# 1616.net
KiCad netlist of a schematic drawn in EAGLE
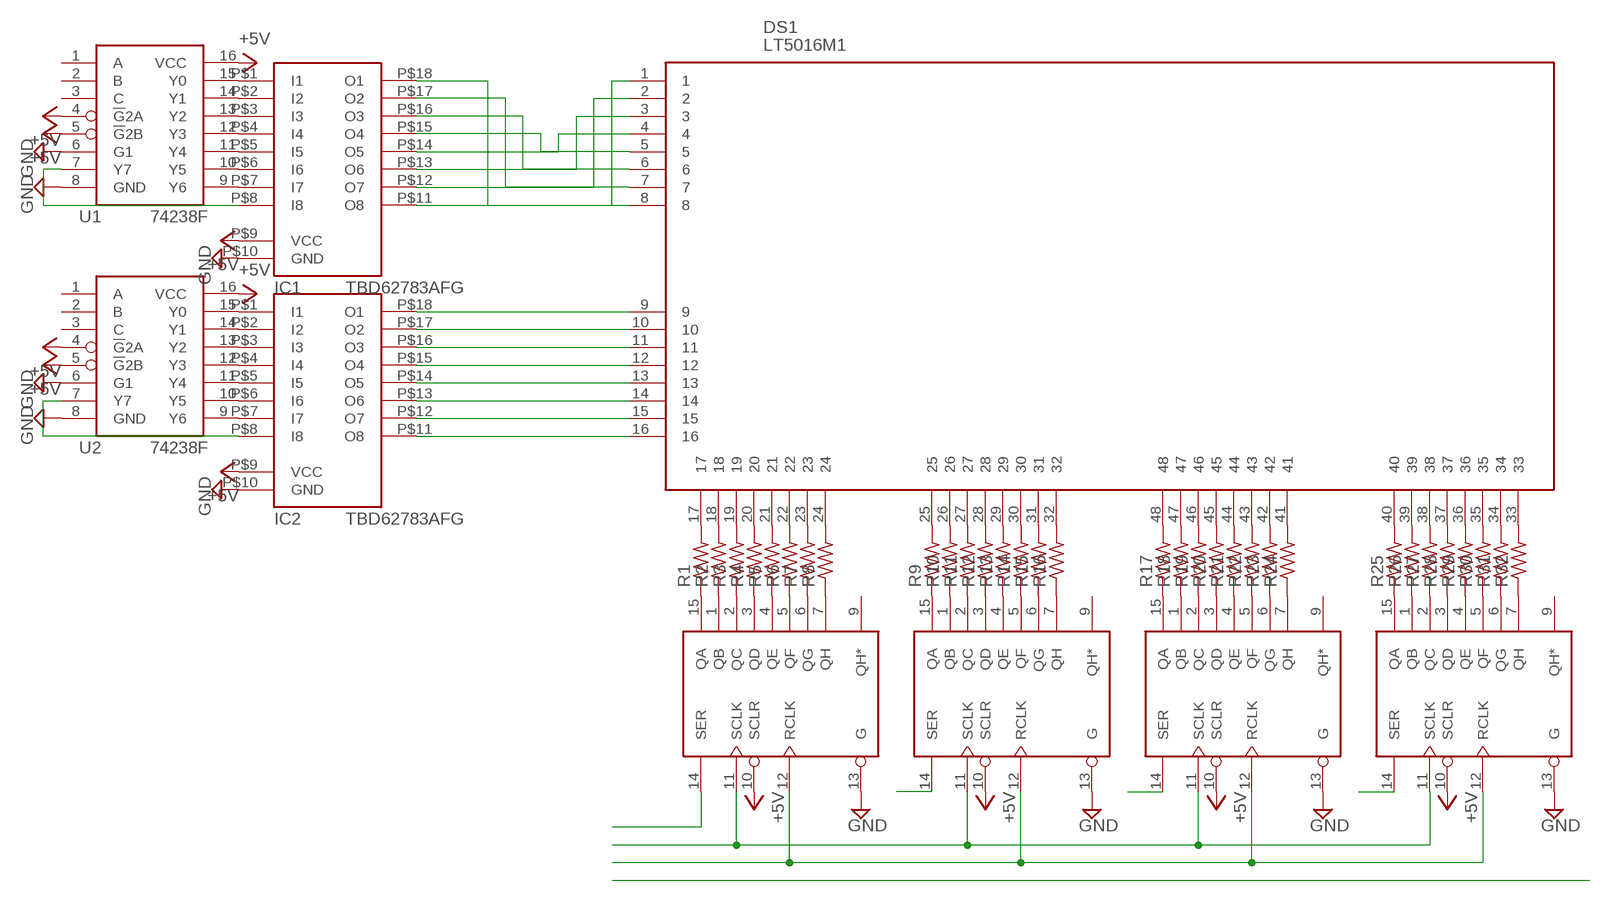
[diagram p0: schematic, sheet 1]

(export (version "E")
  (design (tool "Eeschema 10.0.6"))
  (components
    (comp (ref "DS1")
      (value "LT5016M1")
      (footprint "eagle-import:LT5016M1")
      (libsource (lib "eagle-import") (part "LT5016M1"))
    )
    (comp (ref "IC1")
      (value "TBD62783AFG")
      (footprint "eagle-import:SOP18")
      (libsource (lib "eagle-import") (part "TBD62783AFG"))
    )
    (comp (ref "IC2")
      (value "TBD62783AFG")
      (footprint "eagle-import:SOP18")
      (libsource (lib "eagle-import") (part "TBD62783AFG"))
    )
    (comp (ref "R1")
      (value "R-2012")
      (footprint "eagle-import:2012-R")
      (libsource (lib "eagle-import") (part "R-2012"))
    )
    (comp (ref "R2")
      (value "R-2012")
      (footprint "eagle-import:2012-R")
      (libsource (lib "eagle-import") (part "R-2012"))
    )
    (comp (ref "R3")
      (value "R-2012")
      (footprint "eagle-import:2012-R")
      (libsource (lib "eagle-import") (part "R-2012"))
    )
    (comp (ref "R4")
      (value "R-2012")
      (footprint "eagle-import:2012-R")
      (libsource (lib "eagle-import") (part "R-2012"))
    )
    (comp (ref "R5")
      (value "R-2012")
      (footprint "eagle-import:2012-R")
      (libsource (lib "eagle-import") (part "R-2012"))
    )
    (comp (ref "R6")
      (value "R-2012")
      (footprint "eagle-import:2012-R")
      (libsource (lib "eagle-import") (part "R-2012"))
    )
    (comp (ref "R7")
      (value "R-2012")
      (footprint "eagle-import:2012-R")
      (libsource (lib "eagle-import") (part "R-2012"))
    )
    (comp (ref "R8")
      (value "R-2012")
      (footprint "eagle-import:2012-R")
      (libsource (lib "eagle-import") (part "R-2012"))
    )
    (comp (ref "R9")
      (value "R-2012")
      (footprint "eagle-import:2012-R")
      (libsource (lib "eagle-import") (part "R-2012"))
    )
    (comp (ref "R10")
      (value "R-2012")
      (footprint "eagle-import:2012-R")
      (libsource (lib "eagle-import") (part "R-2012"))
    )
    (comp (ref "R11")
      (value "R-2012")
      (footprint "eagle-import:2012-R")
      (libsource (lib "eagle-import") (part "R-2012"))
    )
    (comp (ref "R12")
      (value "R-2012")
      (footprint "eagle-import:2012-R")
      (libsource (lib "eagle-import") (part "R-2012"))
    )
    (comp (ref "R13")
      (value "R-2012")
      (footprint "eagle-import:2012-R")
      (libsource (lib "eagle-import") (part "R-2012"))
    )
    (comp (ref "R14")
      (value "R-2012")
      (footprint "eagle-import:2012-R")
      (libsource (lib "eagle-import") (part "R-2012"))
    )
    (comp (ref "R15")
      (value "R-2012")
      (footprint "eagle-import:2012-R")
      (libsource (lib "eagle-import") (part "R-2012"))
    )
    (comp (ref "R16")
      (value "R-2012")
      (footprint "eagle-import:2012-R")
      (libsource (lib "eagle-import") (part "R-2012"))
    )
    (comp (ref "R17")
      (value "R-2012")
      (footprint "eagle-import:2012-R")
      (libsource (lib "eagle-import") (part "R-2012"))
    )
    (comp (ref "R18")
      (value "R-2012")
      (footprint "eagle-import:2012-R")
      (libsource (lib "eagle-import") (part "R-2012"))
    )
    (comp (ref "R19")
      (value "R-2012")
      (footprint "eagle-import:2012-R")
      (libsource (lib "eagle-import") (part "R-2012"))
    )
    (comp (ref "R20")
      (value "R-2012")
      (footprint "eagle-import:2012-R")
      (libsource (lib "eagle-import") (part "R-2012"))
    )
    (comp (ref "R21")
      (value "R-2012")
      (footprint "eagle-import:2012-R")
      (libsource (lib "eagle-import") (part "R-2012"))
    )
    (comp (ref "R22")
      (value "R-2012")
      (footprint "eagle-import:2012-R")
      (libsource (lib "eagle-import") (part "R-2012"))
    )
    (comp (ref "R23")
      (value "R-2012")
      (footprint "eagle-import:2012-R")
      (libsource (lib "eagle-import") (part "R-2012"))
    )
    (comp (ref "R24")
      (value "R-2012")
      (footprint "eagle-import:2012-R")
      (libsource (lib "eagle-import") (part "R-2012"))
    )
    (comp (ref "R25")
      (value "R-2012")
      (footprint "eagle-import:2012-R")
      (libsource (lib "eagle-import") (part "R-2012"))
    )
    (comp (ref "R26")
      (value "R-2012")
      (footprint "eagle-import:2012-R")
      (libsource (lib "eagle-import") (part "R-2012"))
    )
    (comp (ref "R27")
      (value "R-2012")
      (footprint "eagle-import:2012-R")
      (libsource (lib "eagle-import") (part "R-2012"))
    )
    (comp (ref "R28")
      (value "R-2012")
      (footprint "eagle-import:2012-R")
      (libsource (lib "eagle-import") (part "R-2012"))
    )
    (comp (ref "R29")
      (value "R-2012")
      (footprint "eagle-import:2012-R")
      (libsource (lib "eagle-import") (part "R-2012"))
    )
    (comp (ref "R30")
      (value "R-2012")
      (footprint "eagle-import:2012-R")
      (libsource (lib "eagle-import") (part "R-2012"))
    )
    (comp (ref "R31")
      (value "R-2012")
      (footprint "eagle-import:2012-R")
      (libsource (lib "eagle-import") (part "R-2012"))
    )
    (comp (ref "R32")
      (value "R-2012")
      (footprint "eagle-import:2012-R")
      (libsource (lib "eagle-import") (part "R-2012"))
    )
    (comp (ref "U$1")
      (value "74HC595N")
      (footprint "eagle-import:DIL16")
      (libsource (lib "eagle-import") (part "74595NHC"))
    )
    (comp (ref "U$2")
      (value "74HC595N")
      (footprint "eagle-import:DIL16")
      (libsource (lib "eagle-import") (part "74595NHC"))
    )
    (comp (ref "U$3")
      (value "74HC595N")
      (footprint "eagle-import:DIL16")
      (libsource (lib "eagle-import") (part "74595NHC"))
    )
    (comp (ref "U$4")
      (value "74HC595N")
      (footprint "eagle-import:DIL16")
      (libsource (lib "eagle-import") (part "74595NHC"))
    )
    (comp (ref "U1")
      (value "74238F")
      (footprint "eagle-import:SOP16")
      (libsource (lib "eagle-import") (part "74238F"))
    )
    (comp (ref "U2")
      (value "74238F")
      (footprint "eagle-import:SOP16")
      (libsource (lib "eagle-import") (part "74238F"))
    )
  )
  (nets
    (net (code "1") (name "+5V") (class "Default")
      (node (ref "IC1") (pin "P$9") (pinfunction "VCC_P$9") (pintype "power_in"))
      (node (ref "IC2") (pin "P$9") (pinfunction "VCC_P$9") (pintype "power_in"))
      (node (ref "U$1") (pin "10") (pinfunction "SCLR_10") (pintype "input"))
      (node (ref "U$2") (pin "10") (pinfunction "SCLR_10") (pintype "input"))
      (node (ref "U$3") (pin "10") (pinfunction "SCLR_10") (pintype "input"))
      (node (ref "U$4") (pin "10") (pinfunction "SCLR_10") (pintype "input"))
      (node (ref "U1") (pin "16") (pinfunction "VCC_16") (pintype "power_in"))
      (node (ref "U1") (pin "4") (pinfunction "~{G}2A_4") (pintype "input"))
      (node (ref "U1") (pin "5") (pinfunction "~{G}2B_5") (pintype "input"))
      (node (ref "U2") (pin "16") (pinfunction "VCC_16") (pintype "power_in"))
      (node (ref "U2") (pin "4") (pinfunction "~{G}2A_4") (pintype "input"))
      (node (ref "U2") (pin "5") (pinfunction "~{G}2B_5") (pintype "input"))
    )
    (net (code "2") (name "GND") (class "Default")
      (node (ref "IC1") (pin "P$10") (pinfunction "GND_P$10") (pintype "power_in"))
      (node (ref "IC2") (pin "P$10") (pinfunction "GND_P$10") (pintype "power_in"))
      (node (ref "U$1") (pin "13") (pinfunction "G_13") (pintype "input"))
      (node (ref "U$2") (pin "13") (pinfunction "G_13") (pintype "input"))
      (node (ref "U$3") (pin "13") (pinfunction "G_13") (pintype "input"))
      (node (ref "U$4") (pin "13") (pinfunction "G_13") (pintype "input"))
      (node (ref "U1") (pin "6") (pinfunction "G1_6") (pintype "input"))
      (node (ref "U1") (pin "8") (pinfunction "GND_8") (pintype "power_in"))
      (node (ref "U2") (pin "6") (pinfunction "G1_6") (pintype "input"))
      (node (ref "U2") (pin "8") (pinfunction "GND_8") (pintype "power_in"))
    )
    (net (code "3") (name "Net-(DS1-Pad17)") (class "Default")
      (node (ref "DS1") (pin "17") (pinfunction "17_17") (pintype "bidirectional"))
      (node (ref "R1") (pin "2") (pinfunction "2_2") (pintype "passive"))
    )
    (net (code "4") (name "Net-(DS1-Pad18)") (class "Default")
      (node (ref "DS1") (pin "18") (pinfunction "18_18") (pintype "bidirectional"))
      (node (ref "R2") (pin "2") (pinfunction "2_2") (pintype "passive"))
    )
    (net (code "5") (name "Net-(DS1-Pad19)") (class "Default")
      (node (ref "DS1") (pin "19") (pinfunction "19_19") (pintype "bidirectional"))
      (node (ref "R3") (pin "2") (pinfunction "2_2") (pintype "passive"))
    )
    (net (code "6") (name "Net-(DS1-Pad20)") (class "Default")
      (node (ref "DS1") (pin "20") (pinfunction "20_20") (pintype "bidirectional"))
      (node (ref "R4") (pin "2") (pinfunction "2_2") (pintype "passive"))
    )
    (net (code "7") (name "Net-(DS1-Pad21)") (class "Default")
      (node (ref "DS1") (pin "21") (pinfunction "21_21") (pintype "bidirectional"))
      (node (ref "R5") (pin "2") (pinfunction "2_2") (pintype "passive"))
    )
    (net (code "8") (name "Net-(DS1-Pad22)") (class "Default")
      (node (ref "DS1") (pin "22") (pinfunction "22_22") (pintype "bidirectional"))
      (node (ref "R6") (pin "2") (pinfunction "2_2") (pintype "passive"))
    )
    (net (code "9") (name "Net-(DS1-Pad23)") (class "Default")
      (node (ref "DS1") (pin "23") (pinfunction "23_23") (pintype "bidirectional"))
      (node (ref "R7") (pin "2") (pinfunction "2_2") (pintype "passive"))
    )
    (net (code "10") (name "Net-(DS1-Pad24)") (class "Default")
      (node (ref "DS1") (pin "24") (pinfunction "24_24") (pintype "bidirectional"))
      (node (ref "R8") (pin "2") (pinfunction "2_2") (pintype "passive"))
    )
    (net (code "11") (name "Net-(DS1-Pad25)") (class "Default")
      (node (ref "DS1") (pin "25") (pinfunction "25_25") (pintype "bidirectional"))
      (node (ref "R9") (pin "2") (pinfunction "2_2") (pintype "passive"))
    )
    (net (code "12") (name "Net-(DS1-Pad26)") (class "Default")
      (node (ref "DS1") (pin "26") (pinfunction "26_26") (pintype "bidirectional"))
      (node (ref "R10") (pin "2") (pinfunction "2_2") (pintype "passive"))
    )
    (net (code "13") (name "Net-(DS1-Pad27)") (class "Default")
      (node (ref "DS1") (pin "27") (pinfunction "27_27") (pintype "bidirectional"))
      (node (ref "R11") (pin "2") (pinfunction "2_2") (pintype "passive"))
    )
    (net (code "14") (name "Net-(DS1-Pad28)") (class "Default")
      (node (ref "DS1") (pin "28") (pinfunction "28_28") (pintype "bidirectional"))
      (node (ref "R12") (pin "2") (pinfunction "2_2") (pintype "passive"))
    )
    (net (code "15") (name "Net-(DS1-Pad29)") (class "Default")
      (node (ref "DS1") (pin "29") (pinfunction "29_29") (pintype "bidirectional"))
      (node (ref "R13") (pin "2") (pinfunction "2_2") (pintype "passive"))
    )
    (net (code "16") (name "Net-(DS1-Pad30)") (class "Default")
      (node (ref "DS1") (pin "30") (pinfunction "30_30") (pintype "bidirectional"))
      (node (ref "R14") (pin "2") (pinfunction "2_2") (pintype "passive"))
    )
    (net (code "17") (name "Net-(DS1-Pad31)") (class "Default")
      (node (ref "DS1") (pin "31") (pinfunction "31_31") (pintype "bidirectional"))
      (node (ref "R15") (pin "2") (pinfunction "2_2") (pintype "passive"))
    )
    (net (code "18") (name "Net-(DS1-Pad32)") (class "Default")
      (node (ref "DS1") (pin "32") (pinfunction "32_32") (pintype "bidirectional"))
      (node (ref "R16") (pin "2") (pinfunction "2_2") (pintype "passive"))
    )
    (net (code "19") (name "Net-(DS1-Pad33)") (class "Default")
      (node (ref "DS1") (pin "33") (pinfunction "33_33") (pintype "bidirectional"))
      (node (ref "R32") (pin "2") (pinfunction "2_2") (pintype "passive"))
    )
    (net (code "20") (name "Net-(DS1-Pad34)") (class "Default")
      (node (ref "DS1") (pin "34") (pinfunction "34_34") (pintype "bidirectional"))
      (node (ref "R31") (pin "2") (pinfunction "2_2") (pintype "passive"))
    )
    (net (code "21") (name "Net-(DS1-Pad35)") (class "Default")
      (node (ref "DS1") (pin "35") (pinfunction "35_35") (pintype "bidirectional"))
      (node (ref "R30") (pin "2") (pinfunction "2_2") (pintype "passive"))
    )
    (net (code "22") (name "Net-(DS1-Pad36)") (class "Default")
      (node (ref "DS1") (pin "36") (pinfunction "36_36") (pintype "bidirectional"))
      (node (ref "R29") (pin "2") (pinfunction "2_2") (pintype "passive"))
    )
    (net (code "23") (name "Net-(DS1-Pad37)") (class "Default")
      (node (ref "DS1") (pin "37") (pinfunction "37_37") (pintype "bidirectional"))
      (node (ref "R28") (pin "2") (pinfunction "2_2") (pintype "passive"))
    )
    (net (code "24") (name "Net-(DS1-Pad38)") (class "Default")
      (node (ref "DS1") (pin "38") (pinfunction "38_38") (pintype "bidirectional"))
      (node (ref "R27") (pin "2") (pinfunction "2_2") (pintype "passive"))
    )
    (net (code "25") (name "Net-(DS1-Pad39)") (class "Default")
      (node (ref "DS1") (pin "39") (pinfunction "39_39") (pintype "bidirectional"))
      (node (ref "R26") (pin "2") (pinfunction "2_2") (pintype "passive"))
    )
    (net (code "26") (name "Net-(DS1-Pad40)") (class "Default")
      (node (ref "DS1") (pin "40") (pinfunction "40_40") (pintype "bidirectional"))
      (node (ref "R25") (pin "2") (pinfunction "2_2") (pintype "passive"))
    )
    (net (code "27") (name "Net-(DS1-Pad41)") (class "Default")
      (node (ref "DS1") (pin "41") (pinfunction "41_41") (pintype "bidirectional"))
      (node (ref "R24") (pin "2") (pinfunction "2_2") (pintype "passive"))
    )
    (net (code "28") (name "Net-(DS1-Pad42)") (class "Default")
      (node (ref "DS1") (pin "42") (pinfunction "42_42") (pintype "bidirectional"))
      (node (ref "R23") (pin "2") (pinfunction "2_2") (pintype "passive"))
    )
    (net (code "29") (name "Net-(DS1-Pad43)") (class "Default")
      (node (ref "DS1") (pin "43") (pinfunction "43_43") (pintype "bidirectional"))
      (node (ref "R22") (pin "2") (pinfunction "2_2") (pintype "passive"))
    )
    (net (code "30") (name "Net-(DS1-Pad44)") (class "Default")
      (node (ref "DS1") (pin "44") (pinfunction "44_44") (pintype "bidirectional"))
      (node (ref "R21") (pin "2") (pinfunction "2_2") (pintype "passive"))
    )
    (net (code "31") (name "Net-(DS1-Pad45)") (class "Default")
      (node (ref "DS1") (pin "45") (pinfunction "45_45") (pintype "bidirectional"))
      (node (ref "R20") (pin "2") (pinfunction "2_2") (pintype "passive"))
    )
    (net (code "32") (name "Net-(DS1-Pad46)") (class "Default")
      (node (ref "DS1") (pin "46") (pinfunction "46_46") (pintype "bidirectional"))
      (node (ref "R19") (pin "2") (pinfunction "2_2") (pintype "passive"))
    )
    (net (code "33") (name "Net-(DS1-Pad47)") (class "Default")
      (node (ref "DS1") (pin "47") (pinfunction "47_47") (pintype "bidirectional"))
      (node (ref "R18") (pin "2") (pinfunction "2_2") (pintype "passive"))
    )
    (net (code "34") (name "Net-(DS1-Pad48)") (class "Default")
      (node (ref "DS1") (pin "48") (pinfunction "48_48") (pintype "bidirectional"))
      (node (ref "R17") (pin "2") (pinfunction "2_2") (pintype "passive"))
    )
    (net (code "35") (name "Net-(IC1-I1)") (class "Default")
      (node (ref "IC1") (pin "P$1") (pinfunction "I1_P$1") (pintype "input"))
      (node (ref "U1") (pin "15") (pinfunction "Y0_15") (pintype "output"))
    )
    (net (code "36") (name "Net-(IC1-I2)") (class "Default")
      (node (ref "IC1") (pin "P$2") (pinfunction "I2_P$2") (pintype "input"))
      (node (ref "U1") (pin "14") (pinfunction "Y1_14") (pintype "output"))
    )
    (net (code "37") (name "Net-(IC1-I3)") (class "Default")
      (node (ref "IC1") (pin "P$3") (pinfunction "I3_P$3") (pintype "input"))
      (node (ref "U1") (pin "13") (pinfunction "Y2_13") (pintype "output"))
    )
    (net (code "38") (name "Net-(IC1-I4)") (class "Default")
      (node (ref "IC1") (pin "P$4") (pinfunction "I4_P$4") (pintype "input"))
      (node (ref "U1") (pin "12") (pinfunction "Y3_12") (pintype "output"))
    )
    (net (code "39") (name "Net-(IC1-I5)") (class "Default")
      (node (ref "IC1") (pin "P$5") (pinfunction "I5_P$5") (pintype "input"))
      (node (ref "U1") (pin "11") (pinfunction "Y4_11") (pintype "output"))
    )
    (net (code "40") (name "Net-(IC1-I6)") (class "Default")
      (node (ref "IC1") (pin "P$6") (pinfunction "I6_P$6") (pintype "input"))
      (node (ref "U1") (pin "10") (pinfunction "Y5_10") (pintype "output"))
    )
    (net (code "41") (name "Net-(IC1-I7)") (class "Default")
      (node (ref "IC1") (pin "P$7") (pinfunction "I7_P$7") (pintype "input"))
      (node (ref "U1") (pin "9") (pinfunction "Y6_9") (pintype "output"))
    )
    (net (code "42") (name "Net-(IC1-I8)") (class "Default")
      (node (ref "IC1") (pin "P$8") (pinfunction "I8_P$8") (pintype "input"))
      (node (ref "U1") (pin "7") (pinfunction "Y7_7") (pintype "output"))
    )
    (net (code "43") (name "Net-(IC1-O1)") (class "Default")
      (node (ref "DS1") (pin "8") (pinfunction "8_8") (pintype "bidirectional"))
      (node (ref "IC1") (pin "P$18") (pinfunction "O1_P$18") (pintype "output"))
    )
    (net (code "44") (name "Net-(IC1-O2)") (class "Default")
      (node (ref "DS1") (pin "7") (pinfunction "7_7") (pintype "bidirectional"))
      (node (ref "IC1") (pin "P$17") (pinfunction "O2_P$17") (pintype "output"))
    )
    (net (code "45") (name "Net-(IC1-O3)") (class "Default")
      (node (ref "DS1") (pin "6") (pinfunction "6_6") (pintype "bidirectional"))
      (node (ref "IC1") (pin "P$16") (pinfunction "O3_P$16") (pintype "output"))
    )
    (net (code "46") (name "Net-(IC1-O4)") (class "Default")
      (node (ref "DS1") (pin "5") (pinfunction "5_5") (pintype "bidirectional"))
      (node (ref "IC1") (pin "P$15") (pinfunction "O4_P$15") (pintype "output"))
    )
    (net (code "47") (name "Net-(IC1-O5)") (class "Default")
      (node (ref "DS1") (pin "4") (pinfunction "4_4") (pintype "bidirectional"))
      (node (ref "IC1") (pin "P$14") (pinfunction "O5_P$14") (pintype "output"))
    )
    (net (code "48") (name "Net-(IC1-O6)") (class "Default")
      (node (ref "DS1") (pin "3") (pinfunction "3_3") (pintype "bidirectional"))
      (node (ref "IC1") (pin "P$13") (pinfunction "O6_P$13") (pintype "output"))
    )
    (net (code "49") (name "Net-(IC1-O7)") (class "Default")
      (node (ref "DS1") (pin "2") (pinfunction "2_2") (pintype "bidirectional"))
      (node (ref "IC1") (pin "P$12") (pinfunction "O7_P$12") (pintype "output"))
    )
    (net (code "50") (name "Net-(IC1-O8)") (class "Default")
      (node (ref "DS1") (pin "1") (pinfunction "1_1") (pintype "bidirectional"))
      (node (ref "IC1") (pin "P$11") (pinfunction "O8_P$11") (pintype "output"))
    )
    (net (code "51") (name "Net-(IC2-I1)") (class "Default")
      (node (ref "IC2") (pin "P$1") (pinfunction "I1_P$1") (pintype "input"))
      (node (ref "U2") (pin "15") (pinfunction "Y0_15") (pintype "output"))
    )
    (net (code "52") (name "Net-(IC2-I2)") (class "Default")
      (node (ref "IC2") (pin "P$2") (pinfunction "I2_P$2") (pintype "input"))
      (node (ref "U2") (pin "14") (pinfunction "Y1_14") (pintype "output"))
    )
    (net (code "53") (name "Net-(IC2-I3)") (class "Default")
      (node (ref "IC2") (pin "P$3") (pinfunction "I3_P$3") (pintype "input"))
      (node (ref "U2") (pin "13") (pinfunction "Y2_13") (pintype "output"))
    )
    (net (code "54") (name "Net-(IC2-I4)") (class "Default")
      (node (ref "IC2") (pin "P$4") (pinfunction "I4_P$4") (pintype "input"))
      (node (ref "U2") (pin "12") (pinfunction "Y3_12") (pintype "output"))
    )
    (net (code "55") (name "Net-(IC2-I5)") (class "Default")
      (node (ref "IC2") (pin "P$5") (pinfunction "I5_P$5") (pintype "input"))
      (node (ref "U2") (pin "11") (pinfunction "Y4_11") (pintype "output"))
    )
    (net (code "56") (name "Net-(IC2-I6)") (class "Default")
      (node (ref "IC2") (pin "P$6") (pinfunction "I6_P$6") (pintype "input"))
      (node (ref "U2") (pin "10") (pinfunction "Y5_10") (pintype "output"))
    )
    (net (code "57") (name "Net-(IC2-I7)") (class "Default")
      (node (ref "IC2") (pin "P$7") (pinfunction "I7_P$7") (pintype "input"))
      (node (ref "U2") (pin "9") (pinfunction "Y6_9") (pintype "output"))
    )
    (net (code "58") (name "Net-(IC2-I8)") (class "Default")
      (node (ref "IC2") (pin "P$8") (pinfunction "I8_P$8") (pintype "input"))
      (node (ref "U2") (pin "7") (pinfunction "Y7_7") (pintype "output"))
    )
    (net (code "59") (name "Net-(IC2-O1)") (class "Default")
      (node (ref "DS1") (pin "9") (pinfunction "9_9") (pintype "bidirectional"))
      (node (ref "IC2") (pin "P$18") (pinfunction "O1_P$18") (pintype "output"))
    )
    (net (code "60") (name "Net-(IC2-O2)") (class "Default")
      (node (ref "DS1") (pin "10") (pinfunction "10_10") (pintype "bidirectional"))
      (node (ref "IC2") (pin "P$17") (pinfunction "O2_P$17") (pintype "output"))
    )
    (net (code "61") (name "Net-(IC2-O3)") (class "Default")
      (node (ref "DS1") (pin "11") (pinfunction "11_11") (pintype "bidirectional"))
      (node (ref "IC2") (pin "P$16") (pinfunction "O3_P$16") (pintype "output"))
    )
    (net (code "62") (name "Net-(IC2-O4)") (class "Default")
      (node (ref "DS1") (pin "12") (pinfunction "12_12") (pintype "bidirectional"))
      (node (ref "IC2") (pin "P$15") (pinfunction "O4_P$15") (pintype "output"))
    )
    (net (code "63") (name "Net-(IC2-O5)") (class "Default")
      (node (ref "DS1") (pin "13") (pinfunction "13_13") (pintype "bidirectional"))
      (node (ref "IC2") (pin "P$14") (pinfunction "O5_P$14") (pintype "output"))
    )
    (net (code "64") (name "Net-(IC2-O6)") (class "Default")
      (node (ref "DS1") (pin "14") (pinfunction "14_14") (pintype "bidirectional"))
      (node (ref "IC2") (pin "P$13") (pinfunction "O6_P$13") (pintype "output"))
    )
    (net (code "65") (name "Net-(IC2-O7)") (class "Default")
      (node (ref "DS1") (pin "15") (pinfunction "15_15") (pintype "bidirectional"))
      (node (ref "IC2") (pin "P$12") (pinfunction "O7_P$12") (pintype "output"))
    )
    (net (code "66") (name "Net-(IC2-O8)") (class "Default")
      (node (ref "DS1") (pin "16") (pinfunction "16_16") (pintype "bidirectional"))
      (node (ref "IC2") (pin "P$11") (pinfunction "O8_P$11") (pintype "output"))
    )
    (net (code "67") (name "Net-(U$1A-QA)") (class "Default")
      (node (ref "R1") (pin "1") (pinfunction "1_1") (pintype "passive"))
      (node (ref "U$1") (pin "15") (pinfunction "QA_15") (pintype "output"))
    )
    (net (code "68") (name "Net-(U$1A-QB)") (class "Default")
      (node (ref "R2") (pin "1") (pinfunction "1_1") (pintype "passive"))
      (node (ref "U$1") (pin "1") (pinfunction "QB_1") (pintype "output"))
    )
    (net (code "69") (name "Net-(U$1A-QC)") (class "Default")
      (node (ref "R3") (pin "1") (pinfunction "1_1") (pintype "passive"))
      (node (ref "U$1") (pin "2") (pinfunction "QC_2") (pintype "output"))
    )
    (net (code "70") (name "Net-(U$1A-QD)") (class "Default")
      (node (ref "R4") (pin "1") (pinfunction "1_1") (pintype "passive"))
      (node (ref "U$1") (pin "3") (pinfunction "QD_3") (pintype "output"))
    )
    (net (code "71") (name "Net-(U$1A-QE)") (class "Default")
      (node (ref "R5") (pin "1") (pinfunction "1_1") (pintype "passive"))
      (node (ref "U$1") (pin "4") (pinfunction "QE_4") (pintype "output"))
    )
    (net (code "72") (name "Net-(U$1A-QF)") (class "Default")
      (node (ref "R6") (pin "1") (pinfunction "1_1") (pintype "passive"))
      (node (ref "U$1") (pin "5") (pinfunction "QF_5") (pintype "output"))
    )
    (net (code "73") (name "Net-(U$1A-QG)") (class "Default")
      (node (ref "R7") (pin "1") (pinfunction "1_1") (pintype "passive"))
      (node (ref "U$1") (pin "6") (pinfunction "QG_6") (pintype "output"))
    )
    (net (code "74") (name "Net-(U$1A-QH)") (class "Default")
      (node (ref "R8") (pin "1") (pinfunction "1_1") (pintype "passive"))
      (node (ref "U$1") (pin "7") (pinfunction "QH_7") (pintype "output"))
    )
    (net (code "75") (name "Net-(U$1A-RCLK)") (class "Default")
      (node (ref "U$1") (pin "12") (pinfunction "RCLK_12") (pintype "input"))
      (node (ref "U$2") (pin "12") (pinfunction "RCLK_12") (pintype "input"))
      (node (ref "U$3") (pin "12") (pinfunction "RCLK_12") (pintype "input"))
      (node (ref "U$4") (pin "12") (pinfunction "RCLK_12") (pintype "input"))
    )
    (net (code "76") (name "Net-(U$1A-SCLK)") (class "Default")
      (node (ref "U$1") (pin "11") (pinfunction "SCLK_11") (pintype "input"))
      (node (ref "U$2") (pin "11") (pinfunction "SCLK_11") (pintype "input"))
      (node (ref "U$3") (pin "11") (pinfunction "SCLK_11") (pintype "input"))
      (node (ref "U$4") (pin "11") (pinfunction "SCLK_11") (pintype "input"))
    )
    (net (code "77") (name "Net-(U$2A-QA)") (class "Default")
      (node (ref "R9") (pin "1") (pinfunction "1_1") (pintype "passive"))
      (node (ref "U$2") (pin "15") (pinfunction "QA_15") (pintype "output"))
    )
    (net (code "78") (name "Net-(U$2A-QB)") (class "Default")
      (node (ref "R10") (pin "1") (pinfunction "1_1") (pintype "passive"))
      (node (ref "U$2") (pin "1") (pinfunction "QB_1") (pintype "output"))
    )
    (net (code "79") (name "Net-(U$2A-QC)") (class "Default")
      (node (ref "R11") (pin "1") (pinfunction "1_1") (pintype "passive"))
      (node (ref "U$2") (pin "2") (pinfunction "QC_2") (pintype "output"))
    )
    (net (code "80") (name "Net-(U$2A-QD)") (class "Default")
      (node (ref "R12") (pin "1") (pinfunction "1_1") (pintype "passive"))
      (node (ref "U$2") (pin "3") (pinfunction "QD_3") (pintype "output"))
    )
    (net (code "81") (name "Net-(U$2A-QE)") (class "Default")
      (node (ref "R13") (pin "1") (pinfunction "1_1") (pintype "passive"))
      (node (ref "U$2") (pin "4") (pinfunction "QE_4") (pintype "output"))
    )
    (net (code "82") (name "Net-(U$2A-QF)") (class "Default")
      (node (ref "R14") (pin "1") (pinfunction "1_1") (pintype "passive"))
      (node (ref "U$2") (pin "5") (pinfunction "QF_5") (pintype "output"))
    )
    (net (code "83") (name "Net-(U$2A-QG)") (class "Default")
      (node (ref "R15") (pin "1") (pinfunction "1_1") (pintype "passive"))
      (node (ref "U$2") (pin "6") (pinfunction "QG_6") (pintype "output"))
    )
    (net (code "84") (name "Net-(U$2A-QH)") (class "Default")
      (node (ref "R16") (pin "1") (pinfunction "1_1") (pintype "passive"))
      (node (ref "U$2") (pin "7") (pinfunction "QH_7") (pintype "output"))
    )
    (net (code "85") (name "Net-(U$3A-QA)") (class "Default")
      (node (ref "R17") (pin "1") (pinfunction "1_1") (pintype "passive"))
      (node (ref "U$3") (pin "15") (pinfunction "QA_15") (pintype "output"))
    )
    (net (code "86") (name "Net-(U$3A-QB)") (class "Default")
      (node (ref "R18") (pin "1") (pinfunction "1_1") (pintype "passive"))
      (node (ref "U$3") (pin "1") (pinfunction "QB_1") (pintype "output"))
    )
    (net (code "87") (name "Net-(U$3A-QC)") (class "Default")
      (node (ref "R19") (pin "1") (pinfunction "1_1") (pintype "passive"))
      (node (ref "U$3") (pin "2") (pinfunction "QC_2") (pintype "output"))
    )
    (net (code "88") (name "Net-(U$3A-QD)") (class "Default")
      (node (ref "R20") (pin "1") (pinfunction "1_1") (pintype "passive"))
      (node (ref "U$3") (pin "3") (pinfunction "QD_3") (pintype "output"))
    )
    (net (code "89") (name "Net-(U$3A-QE)") (class "Default")
      (node (ref "R21") (pin "1") (pinfunction "1_1") (pintype "passive"))
      (node (ref "U$3") (pin "4") (pinfunction "QE_4") (pintype "output"))
    )
    (net (code "90") (name "Net-(U$3A-QF)") (class "Default")
      (node (ref "R22") (pin "1") (pinfunction "1_1") (pintype "passive"))
      (node (ref "U$3") (pin "5") (pinfunction "QF_5") (pintype "output"))
    )
    (net (code "91") (name "Net-(U$3A-QG)") (class "Default")
      (node (ref "R23") (pin "1") (pinfunction "1_1") (pintype "passive"))
      (node (ref "U$3") (pin "6") (pinfunction "QG_6") (pintype "output"))
    )
    (net (code "92") (name "Net-(U$3A-QH)") (class "Default")
      (node (ref "R24") (pin "1") (pinfunction "1_1") (pintype "passive"))
      (node (ref "U$3") (pin "7") (pinfunction "QH_7") (pintype "output"))
    )
    (net (code "93") (name "Net-(U$4A-QA)") (class "Default")
      (node (ref "R25") (pin "1") (pinfunction "1_1") (pintype "passive"))
      (node (ref "U$4") (pin "15") (pinfunction "QA_15") (pintype "output"))
    )
    (net (code "94") (name "Net-(U$4A-QB)") (class "Default")
      (node (ref "R26") (pin "1") (pinfunction "1_1") (pintype "passive"))
      (node (ref "U$4") (pin "1") (pinfunction "QB_1") (pintype "output"))
    )
    (net (code "95") (name "Net-(U$4A-QC)") (class "Default")
      (node (ref "R27") (pin "1") (pinfunction "1_1") (pintype "passive"))
      (node (ref "U$4") (pin "2") (pinfunction "QC_2") (pintype "output"))
    )
    (net (code "96") (name "Net-(U$4A-QD)") (class "Default")
      (node (ref "R28") (pin "1") (pinfunction "1_1") (pintype "passive"))
      (node (ref "U$4") (pin "3") (pinfunction "QD_3") (pintype "output"))
    )
    (net (code "97") (name "Net-(U$4A-QE)") (class "Default")
      (node (ref "R29") (pin "1") (pinfunction "1_1") (pintype "passive"))
      (node (ref "U$4") (pin "4") (pinfunction "QE_4") (pintype "output"))
    )
    (net (code "98") (name "Net-(U$4A-QF)") (class "Default")
      (node (ref "R30") (pin "1") (pinfunction "1_1") (pintype "passive"))
      (node (ref "U$4") (pin "5") (pinfunction "QF_5") (pintype "output"))
    )
    (net (code "99") (name "Net-(U$4A-QG)") (class "Default")
      (node (ref "R31") (pin "1") (pinfunction "1_1") (pintype "passive"))
      (node (ref "U$4") (pin "6") (pinfunction "QG_6") (pintype "output"))
    )
    (net (code "100") (name "Net-(U$4A-QH)") (class "Default")
      (node (ref "R32") (pin "1") (pinfunction "1_1") (pintype "passive"))
      (node (ref "U$4") (pin "7") (pinfunction "QH_7") (pintype "output"))
    )
    (net (code "101") (name "unconnected-(U$1A-QH*-Pad9)") (class "Default")
      (node (ref "U$1") (pin "9") (pinfunction "QH*_9") (pintype "output"))
    )
    (net (code "102") (name "unconnected-(U$1A-SER-Pad14)") (class "Default")
      (node (ref "U$1") (pin "14") (pinfunction "SER_14") (pintype "input"))
    )
    (net (code "103") (name "unconnected-(U$2A-QH*-Pad9)") (class "Default")
      (node (ref "U$2") (pin "9") (pinfunction "QH*_9") (pintype "output"))
    )
    (net (code "104") (name "unconnected-(U$2A-SER-Pad14)") (class "Default")
      (node (ref "U$2") (pin "14") (pinfunction "SER_14") (pintype "input"))
    )
    (net (code "105") (name "unconnected-(U$3A-QH*-Pad9)") (class "Default")
      (node (ref "U$3") (pin "9") (pinfunction "QH*_9") (pintype "output"))
    )
    (net (code "106") (name "unconnected-(U$3A-SER-Pad14)") (class "Default")
      (node (ref "U$3") (pin "14") (pinfunction "SER_14") (pintype "input"))
    )
    (net (code "107") (name "unconnected-(U$4A-QH*-Pad9)") (class "Default")
      (node (ref "U$4") (pin "9") (pinfunction "QH*_9") (pintype "output"))
    )
    (net (code "108") (name "unconnected-(U$4A-SER-Pad14)") (class "Default")
      (node (ref "U$4") (pin "14") (pinfunction "SER_14") (pintype "input"))
    )
    (net (code "109") (name "unconnected-(U1-A-Pad1)") (class "Default")
      (node (ref "U1") (pin "1") (pinfunction "A_1") (pintype "input"))
    )
    (net (code "110") (name "unconnected-(U1-B-Pad2)") (class "Default")
      (node (ref "U1") (pin "2") (pinfunction "B_2") (pintype "input"))
    )
    (net (code "111") (name "unconnected-(U1-C-Pad3)") (class "Default")
      (node (ref "U1") (pin "3") (pinfunction "C_3") (pintype "input"))
    )
    (net (code "112") (name "unconnected-(U2-A-Pad1)") (class "Default")
      (node (ref "U2") (pin "1") (pinfunction "A_1") (pintype "input"))
    )
    (net (code "113") (name "unconnected-(U2-B-Pad2)") (class "Default")
      (node (ref "U2") (pin "2") (pinfunction "B_2") (pintype "input"))
    )
    (net (code "114") (name "unconnected-(U2-C-Pad3)") (class "Default")
      (node (ref "U2") (pin "3") (pinfunction "C_3") (pintype "input"))
    )
  )
)
